# hw.net
KiCad netlist of a schematic drawn in EAGLE
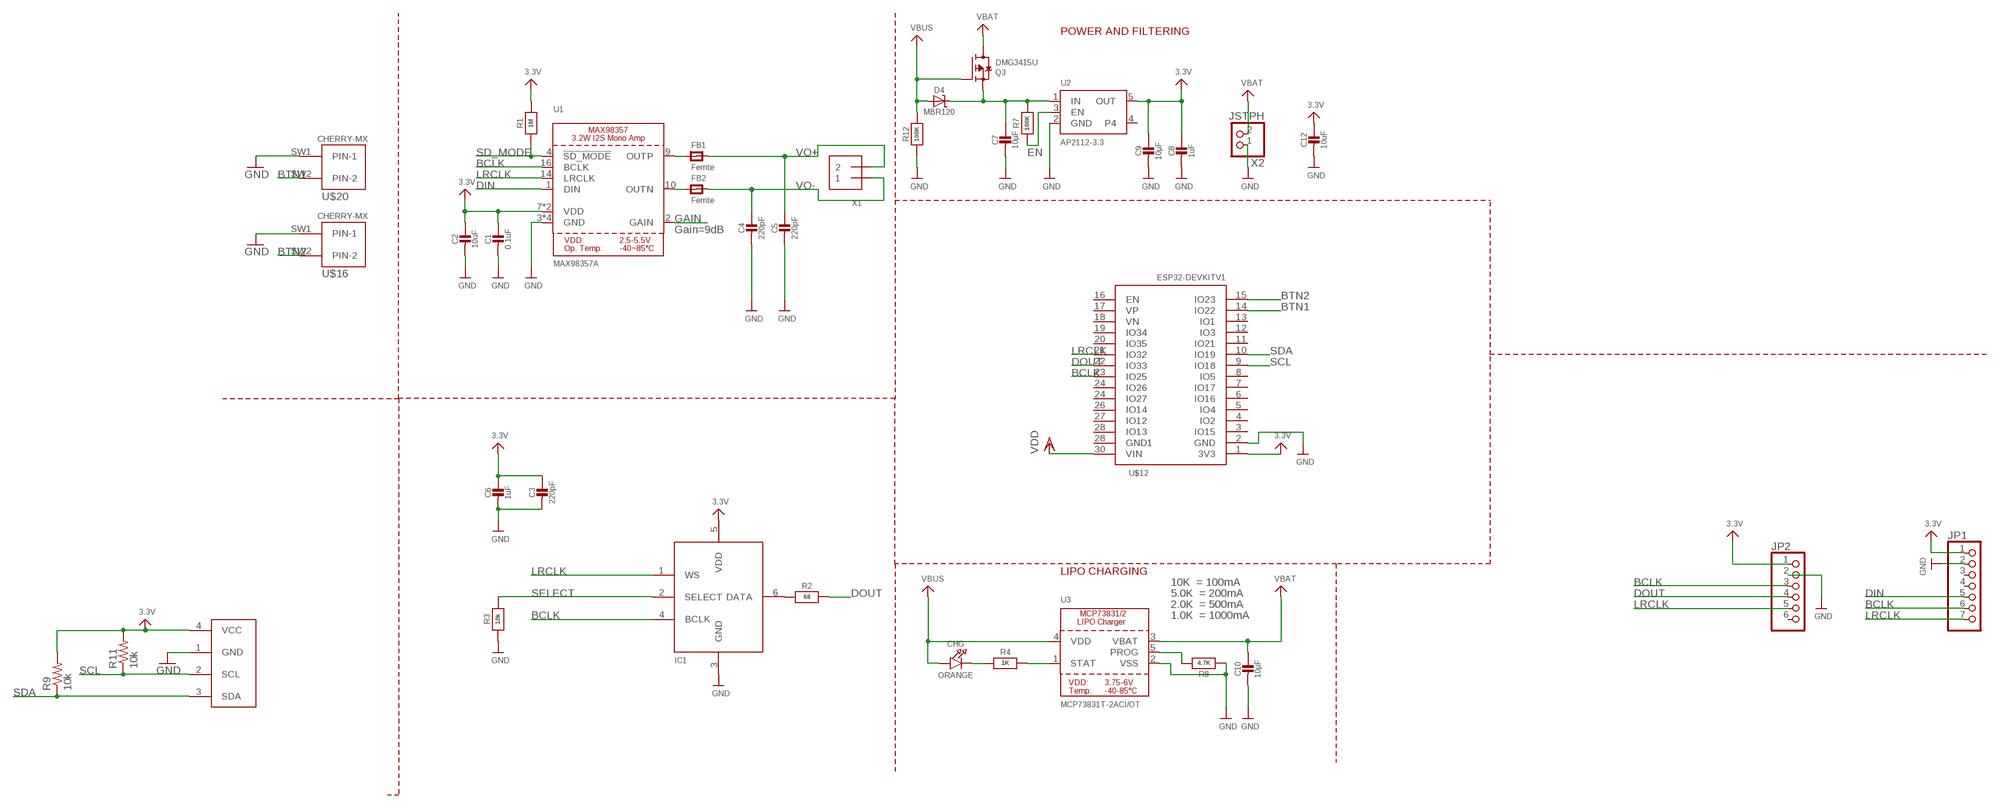
[diagram p0: schematic, sheet 1]

(export (version "E")
  (design (tool "Eeschema 10.0.6"))
  (components
    (comp (ref "C1")
      (value "0.1uF")
      (footprint "eagle-import:0805-NO")
      (libsource (lib "eagle-import") (part "CAP_CERAMIC0805-NOOUTLINE"))
    )
    (comp (ref "C2")
      (value "10uF")
      (footprint "eagle-import:0805-NO")
      (libsource (lib "eagle-import") (part "CAP_CERAMIC0805-NOOUTLINE"))
    )
    (comp (ref "C3")
      (value "220pF")
      (footprint "eagle-import:0805-NO")
      (libsource (lib "eagle-import") (part "CAP_CERAMIC0805-NOOUTLINE"))
    )
    (comp (ref "C4")
      (value "220pF")
      (footprint "eagle-import:0805-NO")
      (libsource (lib "eagle-import") (part "CAP_CERAMIC0805-NOOUTLINE"))
    )
    (comp (ref "C5")
      (value "220pF")
      (footprint "eagle-import:0805-NO")
      (libsource (lib "eagle-import") (part "CAP_CERAMIC0805-NOOUTLINE"))
    )
    (comp (ref "C6")
      (value "1uF")
      (footprint "eagle-import:0805-NO")
      (libsource (lib "eagle-import") (part "CAP_CERAMIC0805-NOOUTLINE"))
    )
    (comp (ref "C7")
      (value "10µF")
      (footprint "eagle-import:0805-NO")
      (libsource (lib "eagle-import") (part "CAP_CERAMIC0805-NOOUTLINE"))
    )
    (comp (ref "C8")
      (value "1uF")
      (footprint "eagle-import:0603-NO")
      (libsource (lib "eagle-import") (part "CAP_CERAMIC0603_NO"))
    )
    (comp (ref "C9")
      (value "10µF")
      (footprint "eagle-import:0805-NO")
      (libsource (lib "eagle-import") (part "CAP_CERAMIC0805-NOOUTLINE"))
    )
    (comp (ref "C10")
      (value "10µF")
      (footprint "eagle-import:0805-NO")
      (libsource (lib "eagle-import") (part "CAP_CERAMIC0805-NOOUTLINE"))
    )
    (comp (ref "C12")
      (value "10uF")
      (footprint "eagle-import:0805-NO")
      (libsource (lib "eagle-import") (part "CAP_CERAMIC0805-NOOUTLINE"))
    )
    (comp (ref "CHG")
      (value "ORANGE")
      (footprint "eagle-import:CHIPLED_0805_NOOUTLINE")
      (libsource (lib "eagle-import") (part "LED0805_NOOUTLINE"))
    )
    (comp (ref "D4")
      (value "MBR120")
      (footprint "eagle-import:SOD-123")
      (libsource (lib "eagle-import") (part "DIODE-SCHOTTKYSOD-123"))
    )
    (comp (ref "FB1")
      (value "Ferrite")
      (footprint "eagle-import:0805-NO")
      (libsource (lib "eagle-import") (part "FERRITE-0805NO"))
    )
    (comp (ref "FB2")
      (value "Ferrite")
      (footprint "eagle-import:0805-NO")
      (libsource (lib "eagle-import") (part "FERRITE-0805NO"))
    )
    (comp (ref "IC1")
      (value "MIC_I2S_SPH0645")
      (footprint "eagle-import:SPH0645LM4H")
      (libsource (lib "eagle-import") (part "MIC_I2S_SPH0645"))
    )
    (comp (ref "JP1")
      (value "HEADER-1X7THICKER")
      (footprint "eagle-import:1X07_ROUND_76")
      (libsource (lib "eagle-import") (part "HEADER-1X7THICKER"))
    )
    (comp (ref "JP2")
      (value "HEADER-1X6ROUND")
      (footprint "eagle-import:1X06_ROUND")
      (libsource (lib "eagle-import") (part "HEADER-1X6ROUND"))
    )
    (comp (ref "Q3")
      (value "DMG3415U")
      (footprint "eagle-import:SOT23-R")
      (libsource (lib "eagle-import") (part "MOSFET-P"))
    )
    (comp (ref "R1")
      (value "1M")
      (footprint "eagle-import:0805-NO")
      (libsource (lib "eagle-import") (part "RESISTOR0805_NOOUTLINE"))
    )
    (comp (ref "R2")
      (value "68")
      (footprint "eagle-import:0603-NO")
      (libsource (lib "eagle-import") (part "RESISTOR_0603_NOOUT"))
    )
    (comp (ref "R3")
      (value "10k")
      (footprint "eagle-import:0603-NO")
      (libsource (lib "eagle-import") (part "RESISTOR_0603_NOOUT"))
    )
    (comp (ref "R4")
      (value "1K")
      (footprint "eagle-import:0603-NO")
      (libsource (lib "eagle-import") (part "RESISTOR_0603_NOOUT"))
    )
    (comp (ref "R7")
      (value "100K")
      (footprint "eagle-import:0603-NO")
      (libsource (lib "eagle-import") (part "RESISTOR_0603_NOOUT"))
    )
    (comp (ref "R8")
      (value "4.7K")
      (footprint "eagle-import:0603-NO")
      (libsource (lib "eagle-import") (part "RESISTOR_0603_NOOUT"))
    )
    (comp (ref "R9")
      (value "10k")
      (footprint "eagle-import:R0805")
      (libsource (lib "eagle-import") (part "R-US_R0805"))
    )
    (comp (ref "R11")
      (value "10k")
      (footprint "eagle-import:R0805")
      (libsource (lib "eagle-import") (part "R-US_R0805"))
    )
    (comp (ref "R12")
      (value "100K")
      (footprint "eagle-import:0603-NO")
      (libsource (lib "eagle-import") (part "RESISTOR_0603_NOOUT"))
    )
    (comp (ref "U$1")
      (value "I2C_OLED")
      (footprint "eagle-import:I2C_OLED_PACKAGE")
      (libsource (lib "eagle-import") (part "I2C_OLED"))
    )
    (comp (ref "U$12")
      (value "ESP32DEVKITV1")
      (footprint "eagle-import:ESP32-DEVKITV1")
      (libsource (lib "eagle-import") (part "ESP32DEVKITV1"))
    )
    (comp (ref "U$16")
      (value "CHERRY-MX")
      (footprint "eagle-import:CHERRY-MX")
      (libsource (lib "eagle-import") (part "CHERRY-MX"))
    )
    (comp (ref "U$20")
      (value "CHERRY-MX")
      (footprint "eagle-import:CHERRY-MX")
      (libsource (lib "eagle-import") (part "CHERRY-MX"))
    )
    (comp (ref "U1")
      (value "MAX98357A")
      (footprint "eagle-import:QFN16_3MM")
      (libsource (lib "eagle-import") (part "AUDIOAMP_MAX98357"))
    )
    (comp (ref "U2")
      (value "AP2112-3.3")
      (footprint "eagle-import:SOT23-5")
      (libsource (lib "eagle-import") (part "VREG_SOT23-5"))
    )
    (comp (ref "U3")
      (value "MCP73831T-2ACI/OT")
      (footprint "eagle-import:SOT23-5")
      (libsource (lib "eagle-import") (part "MCP73831/2"))
    )
    (comp (ref "X1")
      (value "TERMBLOCK_1X2")
      (footprint "eagle-import:TERMBLOCK_1X2-3.5MM")
      (libsource (lib "eagle-import") (part "TERMBLOCK_1X2"))
    )
    (comp (ref "X2")
      (value "JSTPH")
      (footprint "eagle-import:JSTPH2")
      (libsource (lib "eagle-import") (part "CON_JST_PH_2PIN"))
    )
  )
  (nets
    (net (code "1") (name "/BCLK") (class "Default")
      (node (ref "IC1") (pin "4") (pinfunction "BCLK_4") (pintype "input"))
      (node (ref "JP1") (pin "6") (pinfunction "6_6") (pintype "passive"))
      (node (ref "JP2") (pin "3") (pinfunction "3_3") (pintype "passive"))
      (node (ref "U$12") (pin "23") (pinfunction "IO25_23") (pintype "bidirectional"))
      (node (ref "U1") (pin "16") (pinfunction "BCLK_16") (pintype "bidirectional"))
    )
    (net (code "2") (name "/BTN1") (class "Default")
      (node (ref "U$12") (pin "14") (pinfunction "IO22_14") (pintype "bidirectional"))
      (node (ref "U$20") (pin "SW2") (pinfunction "PIN-2_SW2") (pintype "bidirectional"))
    )
    (net (code "3") (name "/BTN2") (class "Default")
      (node (ref "U$12") (pin "15") (pinfunction "IO23_15") (pintype "bidirectional"))
      (node (ref "U$16") (pin "SW2") (pinfunction "PIN-2_SW2") (pintype "bidirectional"))
    )
    (net (code "4") (name "/DIN") (class "Default")
      (node (ref "JP1") (pin "5") (pinfunction "5_5") (pintype "passive"))
      (node (ref "U1") (pin "1") (pinfunction "DIN_1") (pintype "bidirectional"))
    )
    (net (code "5") (name "/DOUT") (class "Default")
      (node (ref "JP2") (pin "4") (pinfunction "4_4") (pintype "passive"))
      (node (ref "R2") (pin "2") (pinfunction "2_2") (pintype "passive"))
      (node (ref "U$12") (pin "22") (pinfunction "IO33_22") (pintype "bidirectional"))
    )
    (net (code "6") (name "/EN") (class "Default")
      (node (ref "R7") (pin "1") (pinfunction "1_1") (pintype "passive"))
      (node (ref "U2") (pin "3") (pinfunction "EN_3") (pintype "input"))
    )
    (net (code "7") (name "/GAIN") (class "Default")
      (node (ref "U1") (pin "2") (pinfunction "GAIN_2") (pintype "bidirectional"))
    )
    (net (code "8") (name "/LRCLK") (class "Default")
      (node (ref "IC1") (pin "1") (pinfunction "WS_1") (pintype "input"))
      (node (ref "JP1") (pin "7") (pinfunction "7_7") (pintype "passive"))
      (node (ref "JP2") (pin "5") (pinfunction "5_5") (pintype "passive"))
      (node (ref "U$12") (pin "21") (pinfunction "IO32_21") (pintype "bidirectional"))
      (node (ref "U1") (pin "14") (pinfunction "LRCLK_14") (pintype "bidirectional"))
    )
    (net (code "9") (name "/SCL") (class "Default")
      (node (ref "R11") (pin "1") (pinfunction "1_1") (pintype "passive"))
      (node (ref "U$1") (pin "2") (pinfunction "SCL_2") (pintype "bidirectional"))
      (node (ref "U$12") (pin "9") (pinfunction "IO18_9") (pintype "bidirectional"))
    )
    (net (code "10") (name "/SDA") (class "Default")
      (node (ref "R9") (pin "1") (pinfunction "1_1") (pintype "passive"))
      (node (ref "U$1") (pin "3") (pinfunction "SDA_3") (pintype "bidirectional"))
      (node (ref "U$12") (pin "10") (pinfunction "IO19_10") (pintype "bidirectional"))
    )
    (net (code "11") (name "/SD_MODE") (class "Default")
      (node (ref "R1") (pin "1") (pinfunction "1_1") (pintype "passive"))
      (node (ref "U1") (pin "4") (pinfunction "~{SD_MODE}_4") (pintype "bidirectional"))
    )
    (net (code "12") (name "/SELECT") (class "Default")
      (node (ref "IC1") (pin "2") (pinfunction "SELECT_2") (pintype "input"))
      (node (ref "R3") (pin "2") (pinfunction "2_2") (pintype "passive"))
    )
    (net (code "13") (name "/VO+") (class "Default")
      (node (ref "C5") (pin "1") (pinfunction "1_1") (pintype "passive"))
      (node (ref "FB1") (pin "2") (pinfunction "P$2_2") (pintype "passive"))
      (node (ref "X1") (pin "2") (pinfunction "2_2") (pintype "passive"))
    )
    (net (code "14") (name "/VO-") (class "Default")
      (node (ref "C4") (pin "1") (pinfunction "1_1") (pintype "passive"))
      (node (ref "FB2") (pin "2") (pinfunction "P$2_2") (pintype "passive"))
      (node (ref "X1") (pin "1") (pinfunction "1_1") (pintype "passive"))
    )
    (net (code "15") (name "3.3V") (class "Default")
      (node (ref "C1") (pin "1") (pinfunction "1_1") (pintype "passive"))
      (node (ref "C12") (pin "1") (pinfunction "1_1") (pintype "passive"))
      (node (ref "C2") (pin "1") (pinfunction "1_1") (pintype "passive"))
      (node (ref "C3") (pin "1") (pinfunction "1_1") (pintype "passive"))
      (node (ref "C6") (pin "1") (pinfunction "1_1") (pintype "passive"))
      (node (ref "C8") (pin "1") (pinfunction "1_1") (pintype "passive"))
      (node (ref "C9") (pin "1") (pinfunction "1_1") (pintype "passive"))
      (node (ref "IC1") (pin "5") (pinfunction "VDD_5") (pintype "power_in"))
      (node (ref "JP1") (pin "1") (pinfunction "1_1") (pintype "passive"))
      (node (ref "JP2") (pin "1") (pinfunction "1_1") (pintype "passive"))
      (node (ref "R1") (pin "2") (pinfunction "2_2") (pintype "passive"))
      (node (ref "R11") (pin "2") (pinfunction "2_2") (pintype "passive"))
      (node (ref "R9") (pin "2") (pinfunction "2_2") (pintype "passive"))
      (node (ref "U$1") (pin "4") (pinfunction "VCC_4") (pintype "bidirectional"))
      (node (ref "U$12") (pin "1") (pinfunction "3V3_1") (pintype "bidirectional"))
      (node (ref "U1") (pin "7") (pinfunction "VDD_7") (pintype "power_in"))
      (node (ref "U1") (pin "8") (pinfunction "VDD_8") (pintype "power_in"))
      (node (ref "U2") (pin "5") (pinfunction "OUT_5") (pintype "power_in"))
    )
    (net (code "16") (name "GND") (class "Default")
      (node (ref "C1") (pin "2") (pinfunction "2_2") (pintype "passive"))
      (node (ref "C10") (pin "2") (pinfunction "2_2") (pintype "passive"))
      (node (ref "C12") (pin "2") (pinfunction "2_2") (pintype "passive"))
      (node (ref "C2") (pin "2") (pinfunction "2_2") (pintype "passive"))
      (node (ref "C3") (pin "2") (pinfunction "2_2") (pintype "passive"))
      (node (ref "C4") (pin "2") (pinfunction "2_2") (pintype "passive"))
      (node (ref "C5") (pin "2") (pinfunction "2_2") (pintype "passive"))
      (node (ref "C6") (pin "2") (pinfunction "2_2") (pintype "passive"))
      (node (ref "C7") (pin "2") (pinfunction "2_2") (pintype "passive"))
      (node (ref "C8") (pin "2") (pinfunction "2_2") (pintype "passive"))
      (node (ref "C9") (pin "2") (pinfunction "2_2") (pintype "passive"))
      (node (ref "IC1") (pin "3") (pinfunction "GND_3") (pintype "power_in"))
      (node (ref "JP1") (pin "2") (pinfunction "2_2") (pintype "passive"))
      (node (ref "JP2") (pin "2") (pinfunction "2_2") (pintype "passive"))
      (node (ref "R12") (pin "1") (pinfunction "1_1") (pintype "passive"))
      (node (ref "R3") (pin "1") (pinfunction "1_1") (pintype "passive"))
      (node (ref "R8") (pin "1") (pinfunction "1_1") (pintype "passive"))
      (node (ref "U$1") (pin "1") (pinfunction "GND_1") (pintype "bidirectional"))
      (node (ref "U$12") (pin "2") (pinfunction "GND_2") (pintype "bidirectional"))
      (node (ref "U$16") (pin "SW1") (pinfunction "PIN-1_SW1") (pintype "bidirectional"))
      (node (ref "U$20") (pin "SW1") (pinfunction "PIN-1_SW1") (pintype "bidirectional"))
      (node (ref "U1") (pin "11") (pinfunction "GND_11") (pintype "power_in"))
      (node (ref "U1") (pin "15") (pinfunction "GND_15") (pintype "power_in"))
      (node (ref "U1") (pin "3") (pinfunction "GND_3") (pintype "power_in"))
      (node (ref "U1") (pin "THERMAL") (pinfunction "GND_THERMAL") (pintype "power_in"))
      (node (ref "U2") (pin "2") (pinfunction "GND_2") (pintype "power_in"))
      (node (ref "U3") (pin "2") (pinfunction "VSS_2") (pintype "power_in"))
      (node (ref "X2") (pin "1") (pinfunction "1_1") (pintype "passive"))
    )
    (net (code "17") (name "Net-(CHG-PadC)") (class "Default")
      (node (ref "CHG") (pin "C") (pinfunction "C_C") (pintype "passive"))
      (node (ref "R4") (pin "1") (pinfunction "1_1") (pintype "passive"))
    )
    (net (code "18") (name "Net-(FB1-P$1)") (class "Default")
      (node (ref "FB1") (pin "1") (pinfunction "P$1_1") (pintype "passive"))
      (node (ref "U1") (pin "9") (pinfunction "OUTP_9") (pintype "output"))
    )
    (net (code "19") (name "Net-(FB2-P$1)") (class "Default")
      (node (ref "FB2") (pin "1") (pinfunction "P$1_1") (pintype "passive"))
      (node (ref "U1") (pin "10") (pinfunction "OUTN_10") (pintype "output"))
    )
    (net (code "20") (name "Net-(IC1-DATA)") (class "Default")
      (node (ref "IC1") (pin "6") (pinfunction "DATA_6") (pintype "output"))
      (node (ref "R2") (pin "1") (pinfunction "1_1") (pintype "passive"))
    )
    (net (code "21") (name "Net-(Q3-S)") (class "Default")
      (node (ref "C7") (pin "1") (pinfunction "1_1") (pintype "passive"))
      (node (ref "D4") (pin "C") (pinfunction "C_C") (pintype "passive"))
      (node (ref "Q3") (pin "2") (pinfunction "S_2") (pintype "passive"))
      (node (ref "R7") (pin "2") (pinfunction "2_2") (pintype "passive"))
      (node (ref "U2") (pin "1") (pinfunction "IN_1") (pintype "power_in"))
    )
    (net (code "22") (name "Net-(U3-PROG)") (class "Default")
      (node (ref "R8") (pin "2") (pinfunction "2_2") (pintype "passive"))
      (node (ref "U3") (pin "5") (pinfunction "PROG_5") (pintype "input"))
    )
    (net (code "23") (name "Net-(U3-STAT)") (class "Default")
      (node (ref "R4") (pin "2") (pinfunction "2_2") (pintype "passive"))
      (node (ref "U3") (pin "1") (pinfunction "STAT_1") (pintype "output"))
    )
    (net (code "24") (name "VBAT") (class "Default")
      (node (ref "C10") (pin "1") (pinfunction "1_1") (pintype "passive"))
      (node (ref "Q3") (pin "3") (pinfunction "D_3") (pintype "passive"))
      (node (ref "U3") (pin "3") (pinfunction "VBAT_3") (pintype "power_in"))
      (node (ref "X2") (pin "2") (pinfunction "2_2") (pintype "passive"))
    )
    (net (code "25") (name "VBUS") (class "Default")
      (node (ref "CHG") (pin "A") (pinfunction "A_A") (pintype "passive"))
      (node (ref "D4") (pin "A") (pinfunction "A_A") (pintype "passive"))
      (node (ref "Q3") (pin "1") (pinfunction "G_1") (pintype "passive"))
      (node (ref "R12") (pin "2") (pinfunction "2_2") (pintype "passive"))
      (node (ref "U3") (pin "4") (pinfunction "VDD_4") (pintype "power_in"))
    )
    (net (code "26") (name "VDD") (class "Default")
      (node (ref "U$12") (pin "30") (pinfunction "VIN_30") (pintype "bidirectional"))
    )
    (net (code "27") (name "unconnected-(JP1-Pad3)") (class "Default")
      (node (ref "JP1") (pin "3") (pinfunction "3_3") (pintype "passive"))
    )
    (net (code "28") (name "unconnected-(JP1-Pad4)") (class "Default")
      (node (ref "JP1") (pin "4") (pinfunction "4_4") (pintype "passive"))
    )
    (net (code "29") (name "unconnected-(JP2-Pad6)") (class "Default")
      (node (ref "JP2") (pin "6") (pinfunction "6_6") (pintype "passive"))
    )
    (net (code "30") (name "unconnected-(U$12-EN-Pad16)") (class "Default")
      (node (ref "U$12") (pin "16") (pinfunction "EN_16") (pintype "bidirectional"))
    )
    (net (code "31") (name "unconnected-(U$12-GND1-Pad28)") (class "Default")
      (node (ref "U$12") (pin "28") (pinfunction "GND1_28") (pintype "bidirectional"))
    )
    (net (code "32") (name "unconnected-(U$12-IO1-Pad13)") (class "Default")
      (node (ref "U$12") (pin "13") (pinfunction "IO1_13") (pintype "bidirectional"))
    )
    (net (code "33") (name "unconnected-(U$12-IO2-Pad4)") (class "Default")
      (node (ref "U$12") (pin "4") (pinfunction "IO2_4") (pintype "bidirectional"))
    )
    (net (code "34") (name "unconnected-(U$12-IO3-Pad12)") (class "Default")
      (node (ref "U$12") (pin "12") (pinfunction "IO3_12") (pintype "bidirectional"))
    )
    (net (code "35") (name "unconnected-(U$12-IO4-Pad5)") (class "Default")
      (node (ref "U$12") (pin "5") (pinfunction "IO4_5") (pintype "bidirectional"))
    )
    (net (code "36") (name "unconnected-(U$12-IO5-Pad8)") (class "Default")
      (node (ref "U$12") (pin "8") (pinfunction "IO5_8") (pintype "bidirectional"))
    )
    (net (code "37") (name "unconnected-(U$12-IO12-Pad27)") (class "Default")
      (node (ref "U$12") (pin "27") (pinfunction "IO12_27") (pintype "bidirectional"))
    )
    (net (code "38") (name "unconnected-(U$12-IO13-Pad28)") (class "Default")
      (node (ref "U$12") (pin "28") (pinfunction "IO13_28") (pintype "bidirectional"))
    )
    (net (code "39") (name "unconnected-(U$12-IO14-Pad26)") (class "Default")
      (node (ref "U$12") (pin "26") (pinfunction "IO14_26") (pintype "bidirectional"))
    )
    (net (code "40") (name "unconnected-(U$12-IO15-Pad3)") (class "Default")
      (node (ref "U$12") (pin "3") (pinfunction "IO15_3") (pintype "bidirectional"))
    )
    (net (code "41") (name "unconnected-(U$12-IO16-Pad6)") (class "Default")
      (node (ref "U$12") (pin "6") (pinfunction "IO16_6") (pintype "bidirectional"))
    )
    (net (code "42") (name "unconnected-(U$12-IO17-Pad7)") (class "Default")
      (node (ref "U$12") (pin "7") (pinfunction "IO17_7") (pintype "bidirectional"))
    )
    (net (code "43") (name "unconnected-(U$12-IO21-Pad11)") (class "Default")
      (node (ref "U$12") (pin "11") (pinfunction "IO21_11") (pintype "bidirectional"))
    )
    (net (code "44") (name "unconnected-(U$12-IO26-Pad24)") (class "Default")
      (node (ref "U$12") (pin "24") (pinfunction "IO26_24") (pintype "bidirectional"))
    )
    (net (code "45") (name "unconnected-(U$12-IO27-Pad24)") (class "Default")
      (node (ref "U$12") (pin "24") (pinfunction "IO27_24") (pintype "bidirectional"))
    )
    (net (code "46") (name "unconnected-(U$12-IO34-Pad19)") (class "Default")
      (node (ref "U$12") (pin "19") (pinfunction "IO34_19") (pintype "bidirectional"))
    )
    (net (code "47") (name "unconnected-(U$12-IO35-Pad20)") (class "Default")
      (node (ref "U$12") (pin "20") (pinfunction "IO35_20") (pintype "bidirectional"))
    )
    (net (code "48") (name "unconnected-(U$12-VN-Pad18)") (class "Default")
      (node (ref "U$12") (pin "18") (pinfunction "VN_18") (pintype "bidirectional"))
    )
    (net (code "49") (name "unconnected-(U$12-VP-Pad17)") (class "Default")
      (node (ref "U$12") (pin "17") (pinfunction "VP_17") (pintype "bidirectional"))
    )
    (net (code "50") (name "unconnected-(U2-P4-Pad4)") (class "Default")
      (node (ref "U2") (pin "4") (pinfunction "P4_4") (pintype "bidirectional"))
    )
  )
)
